# sunrise_alarmclock.net
KiCad netlist of a schematic drawn in EAGLE
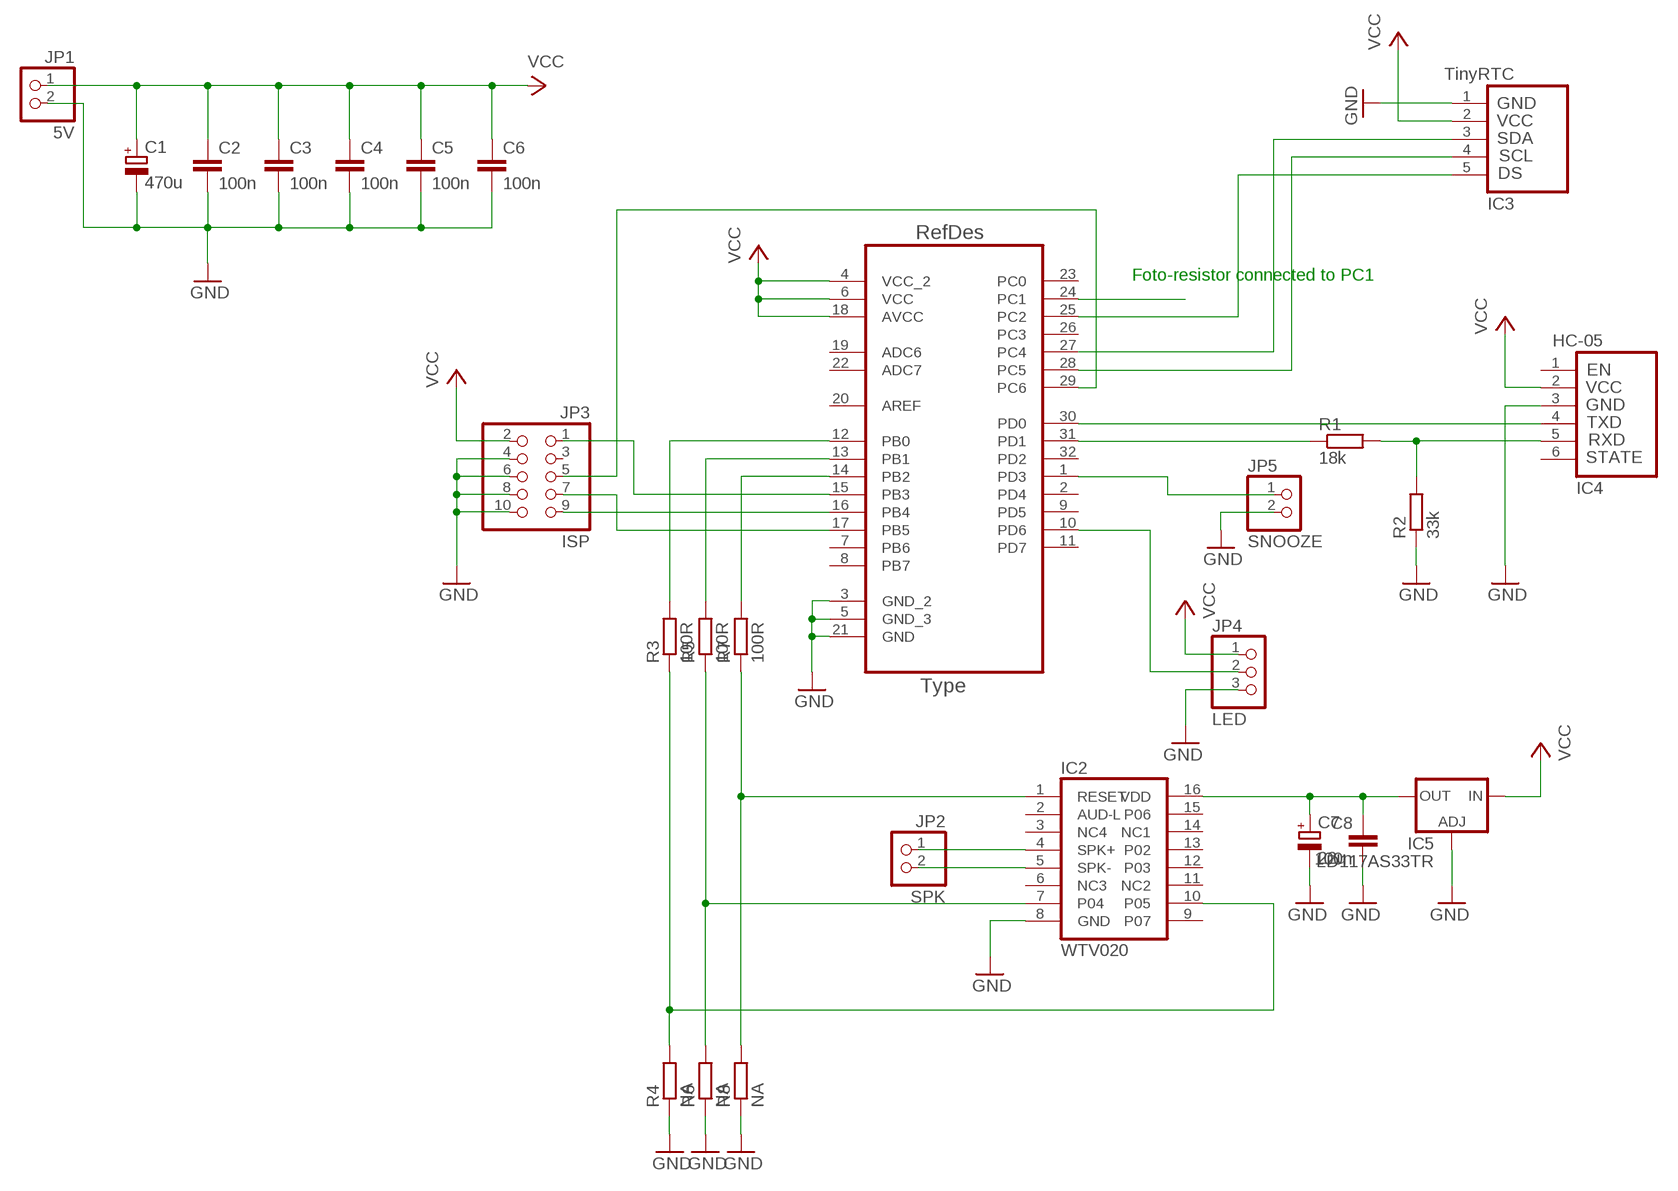
[diagram p0: schematic, sheet 1]

(export (version "E")
  (design (tool "Eeschema 10.0.6"))
  (components
    (comp (ref "C1")
      (value "470u")
      (footprint "eagle-import:D_7343-31W")
      (libsource (lib "eagle-import") (part "CPOL-EUD/7343-31W"))
    )
    (comp (ref "C2")
      (value "100n")
      (footprint "eagle-import:C1206K")
      (libsource (lib "eagle-import") (part "C-EUC1206K"))
    )
    (comp (ref "C3")
      (value "100n")
      (footprint "eagle-import:C1206K")
      (libsource (lib "eagle-import") (part "C-EUC1206K"))
    )
    (comp (ref "C4")
      (value "100n")
      (footprint "eagle-import:C1206K")
      (libsource (lib "eagle-import") (part "C-EUC1206K"))
    )
    (comp (ref "C5")
      (value "100n")
      (footprint "eagle-import:C1206K")
      (libsource (lib "eagle-import") (part "C-EUC1206K"))
    )
    (comp (ref "C6")
      (value "100n")
      (footprint "eagle-import:C1206K")
      (libsource (lib "eagle-import") (part "C-EUC1206K"))
    )
    (comp (ref "C7")
      (value "22u")
      (footprint "eagle-import:C_6032-28R")
      (libsource (lib "eagle-import") (part "CPOL-EUC/6032-28R"))
    )
    (comp (ref "C8")
      (value "100n")
      (footprint "eagle-import:C1206K")
      (libsource (lib "eagle-import") (part "C-EUC1206K"))
    )
    (comp (ref "IC1")
      (value "ATMEGA328P")
      (footprint "eagle-import:QFP80P900X900X120-32N")
      (fields (field (name "MPN") "ATMEGA328P-AU"))
      (libsource (lib "eagle-import") (part "ATMEGA328P-AU"))
    )
    (comp (ref "IC2")
      (value "WTV020")
      (footprint "eagle-import:DIL16-6")
      (libsource (lib "eagle-import") (part "WTV020"))
    )
    (comp (ref "IC3")
      (value "TinyRTC")
      (footprint "eagle-import:HC-05")
      (libsource (lib "eagle-import") (part "TinyRTC_module_HC-05"))
    )
    (comp (ref "IC4")
      (value "HC-05")
      (footprint "eagle-import:HC-05")
      (libsource (lib "eagle-import") (part "HC-05"))
    )
    (comp (ref "IC5")
      (value "LD117AS33TR")
      (footprint "eagle-import:SOT223")
      (libsource (lib "eagle-import") (part "LD117A?S33TR"))
    )
    (comp (ref "JP1")
      (value "5V")
      (footprint "eagle-import:1X02")
      (libsource (lib "eagle-import") (part "PINHD-1X2"))
    )
    (comp (ref "JP2")
      (value "SPK")
      (footprint "eagle-import:1X02")
      (libsource (lib "eagle-import") (part "PINHD-1X2"))
    )
    (comp (ref "JP3")
      (value "ISP")
      (footprint "eagle-import:2X05")
      (libsource (lib "eagle-import") (part "PINHD-2X5"))
    )
    (comp (ref "JP4")
      (value "LED")
      (footprint "eagle-import:1X03")
      (libsource (lib "eagle-import") (part "PINHD-1X3"))
    )
    (comp (ref "JP5")
      (value "SNOOZE")
      (footprint "eagle-import:1X02")
      (libsource (lib "eagle-import") (part "PINHD-1X2"))
    )
    (comp (ref "R1")
      (value "18k")
      (footprint "eagle-import:M1206")
      (libsource (lib "eagle-import") (part "R-EU_M1206"))
    )
    (comp (ref "R2")
      (value "33k")
      (footprint "eagle-import:M1206")
      (libsource (lib "eagle-import") (part "R-EU_M1206"))
    )
    (comp (ref "R3")
      (value "100R")
      (footprint "eagle-import:M1206")
      (libsource (lib "eagle-import") (part "R-EU_M1206"))
    )
    (comp (ref "R4")
      (value "NA")
      (footprint "eagle-import:M1206")
      (libsource (lib "eagle-import") (part "R-EU_M1206"))
    )
    (comp (ref "R5")
      (value "100R")
      (footprint "eagle-import:M1206")
      (libsource (lib "eagle-import") (part "R-EU_M1206"))
    )
    (comp (ref "R6")
      (value "NA")
      (footprint "eagle-import:M1206")
      (libsource (lib "eagle-import") (part "R-EU_M1206"))
    )
    (comp (ref "R7")
      (value "100R")
      (footprint "eagle-import:M1206")
      (libsource (lib "eagle-import") (part "R-EU_M1206"))
    )
    (comp (ref "R8")
      (value "NA")
      (footprint "eagle-import:M1206")
      (libsource (lib "eagle-import") (part "R-EU_M1206"))
    )
  )
  (nets
    (net (code "1") (name "GND") (class "Default")
      (node (ref "C1") (pin "-") (pinfunction "-_-") (pintype "passive"))
      (node (ref "C2") (pin "2") (pinfunction "2_2") (pintype "passive"))
      (node (ref "C3") (pin "2") (pinfunction "2_2") (pintype "passive"))
      (node (ref "C4") (pin "2") (pinfunction "2_2") (pintype "passive"))
      (node (ref "C5") (pin "2") (pinfunction "2_2") (pintype "passive"))
      (node (ref "C6") (pin "2") (pinfunction "2_2") (pintype "passive"))
      (node (ref "C7") (pin "-") (pinfunction "-_-") (pintype "passive"))
      (node (ref "C8") (pin "2") (pinfunction "2_2") (pintype "passive"))
      (node (ref "IC1") (pin "21") (pinfunction "GND_21") (pintype "passive"))
      (node (ref "IC1") (pin "3") (pinfunction "GND_2_3") (pintype "passive"))
      (node (ref "IC1") (pin "5") (pinfunction "GND_3_5") (pintype "passive"))
      (node (ref "IC2") (pin "8") (pinfunction "GND_8") (pintype "input"))
      (node (ref "IC3") (pin "1") (pinfunction "GND_1") (pintype "passive"))
      (node (ref "IC4") (pin "3") (pinfunction "GND_3") (pintype "passive"))
      (node (ref "IC5") (pin "1") (pinfunction "ADJ_1") (pintype "input"))
      (node (ref "JP1") (pin "2") (pinfunction "2_2") (pintype "passive"))
      (node (ref "JP3") (pin "10") (pinfunction "10_10") (pintype "passive"))
      (node (ref "JP3") (pin "4") (pinfunction "4_4") (pintype "passive"))
      (node (ref "JP3") (pin "6") (pinfunction "6_6") (pintype "passive"))
      (node (ref "JP3") (pin "8") (pinfunction "8_8") (pintype "passive"))
      (node (ref "JP4") (pin "3") (pinfunction "3_3") (pintype "passive"))
      (node (ref "JP5") (pin "2") (pinfunction "2_2") (pintype "passive"))
      (node (ref "R2") (pin "1") (pinfunction "1_1") (pintype "passive"))
      (node (ref "R4") (pin "1") (pinfunction "1_1") (pintype "passive"))
      (node (ref "R6") (pin "1") (pinfunction "1_1") (pintype "passive"))
      (node (ref "R8") (pin "1") (pinfunction "1_1") (pintype "passive"))
    )
    (net (code "2") (name "Net-(IC1-PB0)") (class "Default")
      (node (ref "IC1") (pin "12") (pinfunction "PB0_12") (pintype "bidirectional"))
      (node (ref "R3") (pin "2") (pinfunction "2_2") (pintype "passive"))
    )
    (net (code "3") (name "Net-(IC1-PB1)") (class "Default")
      (node (ref "IC1") (pin "13") (pinfunction "PB1_13") (pintype "bidirectional"))
      (node (ref "R5") (pin "2") (pinfunction "2_2") (pintype "passive"))
    )
    (net (code "4") (name "Net-(IC1-PB2)") (class "Default")
      (node (ref "IC1") (pin "14") (pinfunction "PB2_14") (pintype "bidirectional"))
      (node (ref "R7") (pin "2") (pinfunction "2_2") (pintype "passive"))
    )
    (net (code "5") (name "Net-(IC1-PB3)") (class "Default")
      (node (ref "IC1") (pin "15") (pinfunction "PB3_15") (pintype "bidirectional"))
      (node (ref "JP3") (pin "1") (pinfunction "1_1") (pintype "passive"))
    )
    (net (code "6") (name "Net-(IC1-PB4)") (class "Default")
      (node (ref "IC1") (pin "16") (pinfunction "PB4_16") (pintype "bidirectional"))
      (node (ref "JP3") (pin "9") (pinfunction "9_9") (pintype "passive"))
    )
    (net (code "7") (name "Net-(IC1-PB5)") (class "Default")
      (node (ref "IC1") (pin "17") (pinfunction "PB5_17") (pintype "bidirectional"))
      (node (ref "JP3") (pin "7") (pinfunction "7_7") (pintype "passive"))
    )
    (net (code "8") (name "Net-(IC1-PC2)") (class "Default")
      (node (ref "IC1") (pin "25") (pinfunction "PC2_25") (pintype "bidirectional"))
      (node (ref "IC3") (pin "5") (pinfunction "DS_5") (pintype "passive"))
    )
    (net (code "9") (name "Net-(IC1-PC4)") (class "Default")
      (node (ref "IC1") (pin "27") (pinfunction "PC4_27") (pintype "bidirectional"))
      (node (ref "IC3") (pin "3") (pinfunction "SDA_3") (pintype "passive"))
    )
    (net (code "10") (name "Net-(IC1-PC5)") (class "Default")
      (node (ref "IC1") (pin "28") (pinfunction "PC5_28") (pintype "bidirectional"))
      (node (ref "IC3") (pin "4") (pinfunction "SCL_4") (pintype "passive"))
    )
    (net (code "11") (name "Net-(IC1-PC6)") (class "Default")
      (node (ref "IC1") (pin "29") (pinfunction "PC6_29") (pintype "bidirectional"))
      (node (ref "JP3") (pin "5") (pinfunction "5_5") (pintype "passive"))
    )
    (net (code "12") (name "Net-(IC1-PD0)") (class "Default")
      (node (ref "IC1") (pin "30") (pinfunction "PD0_30") (pintype "bidirectional"))
      (node (ref "IC4") (pin "4") (pinfunction "TXD_4") (pintype "passive"))
    )
    (net (code "13") (name "Net-(IC1-PD1)") (class "Default")
      (node (ref "IC1") (pin "31") (pinfunction "PD1_31") (pintype "bidirectional"))
      (node (ref "R1") (pin "1") (pinfunction "1_1") (pintype "passive"))
    )
    (net (code "14") (name "Net-(IC1-PD3)") (class "Default")
      (node (ref "IC1") (pin "1") (pinfunction "PD3_1") (pintype "bidirectional"))
      (node (ref "JP5") (pin "1") (pinfunction "1_1") (pintype "passive"))
    )
    (net (code "15") (name "Net-(IC1-PD6)") (class "Default")
      (node (ref "IC1") (pin "10") (pinfunction "PD6_10") (pintype "bidirectional"))
      (node (ref "JP4") (pin "2") (pinfunction "2_2") (pintype "passive"))
    )
    (net (code "16") (name "Net-(IC2-P04)") (class "Default")
      (node (ref "IC2") (pin "7") (pinfunction "P04_7") (pintype "input"))
      (node (ref "R5") (pin "1") (pinfunction "1_1") (pintype "passive"))
      (node (ref "R6") (pin "2") (pinfunction "2_2") (pintype "passive"))
    )
    (net (code "17") (name "Net-(IC2-P05)") (class "Default")
      (node (ref "IC2") (pin "10") (pinfunction "P05_10") (pintype "input"))
      (node (ref "R3") (pin "1") (pinfunction "1_1") (pintype "passive"))
      (node (ref "R4") (pin "2") (pinfunction "2_2") (pintype "passive"))
    )
    (net (code "18") (name "Net-(IC2-RESET)") (class "Default")
      (node (ref "IC2") (pin "1") (pinfunction "RESET_1") (pintype "input"))
      (node (ref "R7") (pin "1") (pinfunction "1_1") (pintype "passive"))
      (node (ref "R8") (pin "2") (pinfunction "2_2") (pintype "passive"))
    )
    (net (code "19") (name "Net-(IC2-SPK+)") (class "Default")
      (node (ref "IC2") (pin "4") (pinfunction "SPK+_4") (pintype "output"))
      (node (ref "JP2") (pin "1") (pinfunction "1_1") (pintype "passive"))
    )
    (net (code "20") (name "Net-(IC2-SPK-)") (class "Default")
      (node (ref "IC2") (pin "5") (pinfunction "SPK-_5") (pintype "output"))
      (node (ref "JP2") (pin "2") (pinfunction "2_2") (pintype "passive"))
    )
    (net (code "21") (name "Net-(IC2-VDD)") (class "Default")
      (node (ref "C7") (pin "+") (pinfunction "+_+") (pintype "passive"))
      (node (ref "C8") (pin "1") (pinfunction "1_1") (pintype "passive"))
      (node (ref "IC2") (pin "16") (pinfunction "VDD_16") (pintype "power_in"))
      (node (ref "IC5") (pin "4") (pinfunction "OUT_4") (pintype "passive"))
    )
    (net (code "22") (name "Net-(IC4-RXD)") (class "Default")
      (node (ref "IC4") (pin "5") (pinfunction "RXD_5") (pintype "passive"))
      (node (ref "R1") (pin "2") (pinfunction "2_2") (pintype "passive"))
      (node (ref "R2") (pin "2") (pinfunction "2_2") (pintype "passive"))
    )
    (net (code "23") (name "VCC") (class "Default")
      (node (ref "C1") (pin "+") (pinfunction "+_+") (pintype "passive"))
      (node (ref "C2") (pin "1") (pinfunction "1_1") (pintype "passive"))
      (node (ref "C3") (pin "1") (pinfunction "1_1") (pintype "passive"))
      (node (ref "C4") (pin "1") (pinfunction "1_1") (pintype "passive"))
      (node (ref "C5") (pin "1") (pinfunction "1_1") (pintype "passive"))
      (node (ref "C6") (pin "1") (pinfunction "1_1") (pintype "passive"))
      (node (ref "IC1") (pin "18") (pinfunction "AVCC_18") (pintype "power_in"))
      (node (ref "IC1") (pin "4") (pinfunction "VCC_2_4") (pintype "power_in"))
      (node (ref "IC1") (pin "6") (pinfunction "VCC_6") (pintype "power_in"))
      (node (ref "IC3") (pin "2") (pinfunction "VCC_2") (pintype "passive"))
      (node (ref "IC4") (pin "2") (pinfunction "VCC_2") (pintype "passive"))
      (node (ref "IC5") (pin "3") (pinfunction "IN_3") (pintype "input"))
      (node (ref "JP1") (pin "1") (pinfunction "1_1") (pintype "passive"))
      (node (ref "JP3") (pin "2") (pinfunction "2_2") (pintype "passive"))
      (node (ref "JP4") (pin "1") (pinfunction "1_1") (pintype "passive"))
    )
    (net (code "24") (name "unconnected-(IC1-ADC6-Pad19)") (class "Default")
      (node (ref "IC1") (pin "19") (pinfunction "ADC6_19") (pintype "input"))
    )
    (net (code "25") (name "unconnected-(IC1-ADC7-Pad22)") (class "Default")
      (node (ref "IC1") (pin "22") (pinfunction "ADC7_22") (pintype "input"))
    )
    (net (code "26") (name "unconnected-(IC1-AREF-Pad20)") (class "Default")
      (node (ref "IC1") (pin "20") (pinfunction "AREF_20") (pintype "input"))
    )
    (net (code "27") (name "unconnected-(IC1-PB6-Pad7)") (class "Default")
      (node (ref "IC1") (pin "7") (pinfunction "PB6_7") (pintype "bidirectional"))
    )
    (net (code "28") (name "unconnected-(IC1-PB7-Pad8)") (class "Default")
      (node (ref "IC1") (pin "8") (pinfunction "PB7_8") (pintype "bidirectional"))
    )
    (net (code "29") (name "unconnected-(IC1-PC0-Pad23)") (class "Default")
      (node (ref "IC1") (pin "23") (pinfunction "PC0_23") (pintype "bidirectional"))
    )
    (net (code "30") (name "unconnected-(IC1-PC1-Pad24)") (class "Default")
      (node (ref "IC1") (pin "24") (pinfunction "PC1_24") (pintype "bidirectional"))
    )
    (net (code "31") (name "unconnected-(IC1-PC3-Pad26)") (class "Default")
      (node (ref "IC1") (pin "26") (pinfunction "PC3_26") (pintype "bidirectional"))
    )
    (net (code "32") (name "unconnected-(IC1-PD2-Pad32)") (class "Default")
      (node (ref "IC1") (pin "32") (pinfunction "PD2_32") (pintype "bidirectional"))
    )
    (net (code "33") (name "unconnected-(IC1-PD4-Pad2)") (class "Default")
      (node (ref "IC1") (pin "2") (pinfunction "PD4_2") (pintype "bidirectional"))
    )
    (net (code "34") (name "unconnected-(IC1-PD5-Pad9)") (class "Default")
      (node (ref "IC1") (pin "9") (pinfunction "PD5_9") (pintype "bidirectional"))
    )
    (net (code "35") (name "unconnected-(IC1-PD7-Pad11)") (class "Default")
      (node (ref "IC1") (pin "11") (pinfunction "PD7_11") (pintype "bidirectional"))
    )
    (net (code "36") (name "unconnected-(IC2-AUD-L-Pad2)") (class "Default")
      (node (ref "IC2") (pin "2") (pinfunction "AUD-L_2") (pintype "output"))
    )
    (net (code "37") (name "unconnected-(IC2-NC1-Pad14)") (class "Default")
      (node (ref "IC2") (pin "14") (pinfunction "NC1_14") (pintype "no_connect"))
    )
    (net (code "38") (name "unconnected-(IC2-NC2-Pad11)") (class "Default")
      (node (ref "IC2") (pin "11") (pinfunction "NC2_11") (pintype "no_connect"))
    )
    (net (code "39") (name "unconnected-(IC2-NC3-Pad6)") (class "Default")
      (node (ref "IC2") (pin "6") (pinfunction "NC3_6") (pintype "no_connect"))
    )
    (net (code "40") (name "unconnected-(IC2-NC4-Pad3)") (class "Default")
      (node (ref "IC2") (pin "3") (pinfunction "NC4_3") (pintype "no_connect"))
    )
    (net (code "41") (name "unconnected-(IC2-P02-Pad13)") (class "Default")
      (node (ref "IC2") (pin "13") (pinfunction "P02_13") (pintype "input"))
    )
    (net (code "42") (name "unconnected-(IC2-P03-Pad12)") (class "Default")
      (node (ref "IC2") (pin "12") (pinfunction "P03_12") (pintype "input"))
    )
    (net (code "43") (name "unconnected-(IC2-P06-Pad15)") (class "Default")
      (node (ref "IC2") (pin "15") (pinfunction "P06_15") (pintype "output"))
    )
    (net (code "44") (name "unconnected-(IC2-P07-Pad9)") (class "Default")
      (node (ref "IC2") (pin "9") (pinfunction "P07_9") (pintype "input"))
    )
    (net (code "45") (name "unconnected-(IC4-EN-Pad1)") (class "Default")
      (node (ref "IC4") (pin "1") (pinfunction "EN_1") (pintype "passive"))
    )
    (net (code "46") (name "unconnected-(IC4-STATE-Pad6)") (class "Default")
      (node (ref "IC4") (pin "6") (pinfunction "STATE_6") (pintype "passive"))
    )
    (net (code "47") (name "unconnected-(JP3-Pad3)") (class "Default")
      (node (ref "JP3") (pin "3") (pinfunction "3_3") (pintype "passive"))
    )
  )
)
